# OLED.net
KiCad netlist of a schematic drawn in Altium Designer
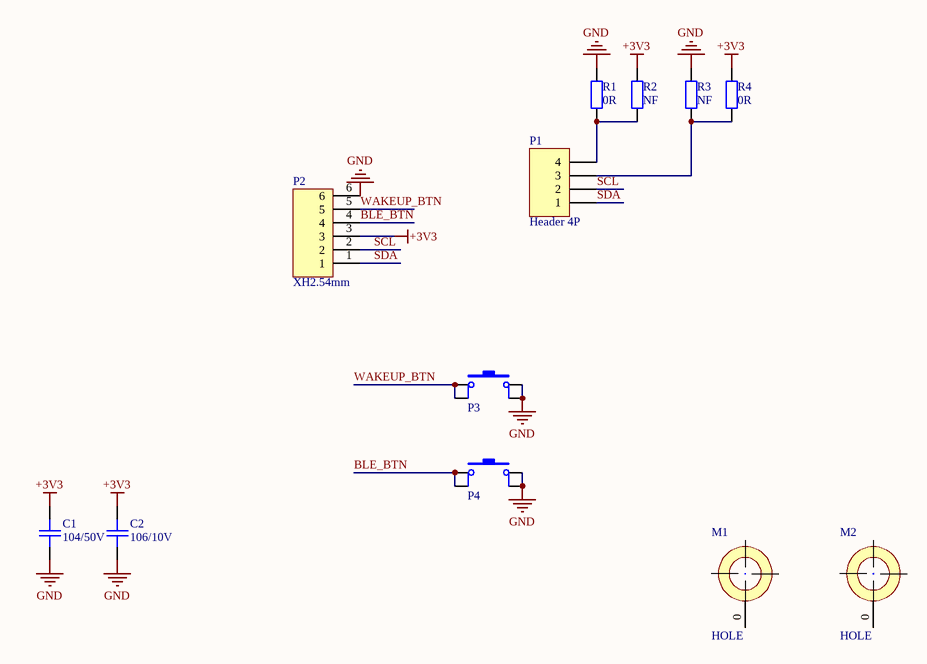
[diagram p0: OLED.SchDoc]

(export (version "E")
  (design (tool "Eeschema 10.0.6"))
  (components
    (comp (ref "C1")
      (value "104/50V")
      (footprint "CAPC-0603 (1608) - HD")
      (description "CAP CER 0.1uF 50V 10% X7R 0603")
      (fields (field (name "MPN") "C0603C104K5RACTU") (field (name "MFR") "KEMET"))
      (libsource (lib "01.Passives 2") (part "C0603C104K5RACTU"))
    )
    (comp (ref "C2")
      (value "106/10V")
      (footprint "CAPC-0603 (1608) - HD")
      (description "CAP CER 10uF 10% 10V X5R 0603")
      (fields (field (name "MPN") "CL10A106KP8NNNC") (field (name "MFR") "Samsung Electro-Mechanics"))
      (libsource (lib "01.Passives 2(1)") (part "CL10A106KP8NNNC"))
    )
    (comp (ref "M1")
      (value "HOLE")
      (footprint "HOLE_3MM_6MM")
      (description "HOLE 2_4/2_5/3_5/3_6")
      (fields (field (name "MPN") "None"))
      (libsource (lib "04.Header-Connecter") (part "HOLE_2_4/2_5/3_5/3_6"))
    )
    (comp (ref "M2")
      (value "HOLE")
      (footprint "HOLE_3MM_6MM")
      (description "HOLE 2_4/2_5/3_5/3_6")
      (fields (field (name "MPN") "None"))
      (libsource (lib "04.Header-Connecter") (part "HOLE_2_4/2_5/3_5/3_6"))
    )
    (comp (ref "P1")
      (value "Header 4P")
      (footprint "HDR1X4")
      (description "Header, 4 Pin Pitch 2.54mm")
      (fields (field (name "MPN") "S1012EC-40-ND"))
      (libsource (lib "04.Header-Connecter") (part "Header 4x1"))
    )
    (comp (ref "P2")
      (value "XH2.54mm")
      (footprint "XH2.54-6p")
      (description "XH2.54mmm - 6P 180 degree")
      (fields (field (name "MPN") "XH2.54-6P") (field (name "MFR") "CHINA"))
      (libsource (lib "04.Header-Connecter") (part "XH2.54-6p"))
    )
    (comp (ref "P3")
      (value "~")
      (footprint "B3F BUTTON")
      (description "BUTTON 12X12X7.3MM")
      (fields (field (name "MPN") "B3F"))
      (libsource (lib "08.Miscellaneous") (part "B3F"))
    )
    (comp (ref "P4")
      (value "~")
      (footprint "B3F BUTTON")
      (description "BUTTON 12X12X7.3MM")
      (fields (field (name "MPN") "B3F"))
      (libsource (lib "08.Miscellaneous") (part "B3F"))
    )
    (comp (ref "R1")
      (value "0R")
      (footprint "RESC-0603 (1608) - HD")
      (description "RES SMD 0.0OHM JUMPER 1/10W 0603")
      (fields (field (name "MPN") "RC0603FR-070RL") (field (name "MFR") "Yageo"))
      (libsource (lib "01.Passives 2(1)") (part "RC0603FR-070RL"))
    )
    (comp (ref "R2")
      (value "NF")
      (footprint "RESC-0603 (1608) - HD")
      (description "RES SMD 0.0OHM JUMPER 1/10W 0603")
      (fields (field (name "MPN") "RC0603FR-070RL") (field (name "MFR") "Yageo"))
      (libsource (lib "01.Passives 2(1)") (part "RC0603FR-070RL"))
    )
    (comp (ref "R3")
      (value "NF")
      (footprint "RESC-0603 (1608) - HD")
      (description "RES SMD 0.0OHM JUMPER 1/10W 0603")
      (fields (field (name "MPN") "RC0603FR-070RL") (field (name "MFR") "Yageo"))
      (libsource (lib "01.Passives 2(1)") (part "RC0603FR-070RL"))
    )
    (comp (ref "R4")
      (value "0R")
      (footprint "RESC-0603 (1608) - HD")
      (description "RES SMD 0.0OHM JUMPER 1/10W 0603")
      (fields (field (name "MPN") "RC0603FR-070RL") (field (name "MFR") "Yageo"))
      (libsource (lib "01.Passives 2(1)") (part "RC0603FR-070RL"))
    )
  )
  (nets
    (net (code "1") (name "+3V3") (class "Default")
      (node (ref "C1") (pin "2") (pinfunction "2_2") (pintype "passive"))
      (node (ref "C2") (pin "2") (pinfunction "2_2") (pintype "passive"))
      (node (ref "P2") (pin "3") (pinfunction "3_3") (pintype "power_in"))
      (node (ref "R2") (pin "2") (pinfunction "2_2") (pintype "passive"))
      (node (ref "R4") (pin "2") (pinfunction "2_2") (pintype "passive"))
    )
    (net (code "2") (name "/BLE_BTN") (class "Default")
      (node (ref "P2") (pin "4") (pinfunction "4_4") (pintype "power_in"))
      (node (ref "P4") (pin "1") (pinfunction "1_1") (pintype "passive"))
      (node (ref "P4") (pin "2") (pinfunction "2_2") (pintype "passive"))
    )
    (net (code "3") (name "/SCL") (class "Default")
      (node (ref "P1") (pin "2") (pinfunction "2_2") (pintype "passive"))
      (node (ref "P2") (pin "2") (pinfunction "2_2") (pintype "passive"))
    )
    (net (code "4") (name "/SDA") (class "Default")
      (node (ref "P1") (pin "1") (pinfunction "1_1") (pintype "passive"))
      (node (ref "P2") (pin "1") (pinfunction "1_1") (pintype "passive"))
    )
    (net (code "5") (name "/WAKEUP_BTN") (class "Default")
      (node (ref "P2") (pin "5") (pinfunction "5_5") (pintype "power_in"))
      (node (ref "P3") (pin "1") (pinfunction "1_1") (pintype "passive"))
      (node (ref "P3") (pin "2") (pinfunction "2_2") (pintype "passive"))
    )
    (net (code "6") (name "GND") (class "Default")
      (node (ref "C1") (pin "1") (pinfunction "1_1") (pintype "passive"))
      (node (ref "C2") (pin "1") (pinfunction "1_1") (pintype "passive"))
      (node (ref "P2") (pin "6") (pinfunction "6_6") (pintype "passive"))
      (node (ref "P3") (pin "2") (pinfunction "2_2") (pintype "passive"))
      (node (ref "P3") (pin "4") (pinfunction "4_4") (pintype "passive"))
      (node (ref "P4") (pin "2") (pinfunction "2_2") (pintype "passive"))
      (node (ref "P4") (pin "4") (pinfunction "4_4") (pintype "passive"))
      (node (ref "R1") (pin "2") (pinfunction "2_2") (pintype "passive"))
      (node (ref "R3") (pin "2") (pinfunction "2_2") (pintype "passive"))
    )
    (net (code "7") (name "Net-(P1-Pad3)") (class "Default")
      (node (ref "P1") (pin "3") (pinfunction "3_3") (pintype "passive"))
      (node (ref "R3") (pin "1") (pinfunction "1_1") (pintype "passive"))
      (node (ref "R4") (pin "1") (pinfunction "1_1") (pintype "passive"))
    )
    (net (code "8") (name "Net-(P1-Pad4)") (class "Default")
      (node (ref "P1") (pin "4") (pinfunction "4_4") (pintype "passive"))
      (node (ref "R1") (pin "1") (pinfunction "1_1") (pintype "passive"))
      (node (ref "R2") (pin "1") (pinfunction "1_1") (pintype "passive"))
    )
    (net (code "9") (name "unconnected-(M1-Pad0)") (class "Default")
      (node (ref "M1") (pin "0") (pinfunction "0_0") (pintype "passive"))
    )
    (net (code "10") (name "unconnected-(M2-Pad0)") (class "Default")
      (node (ref "M2") (pin "0") (pinfunction "0_0") (pintype "passive"))
    )
  )
)
